# LED_drivers.net
KiCad netlist of a schematic drawn in Altium Designer
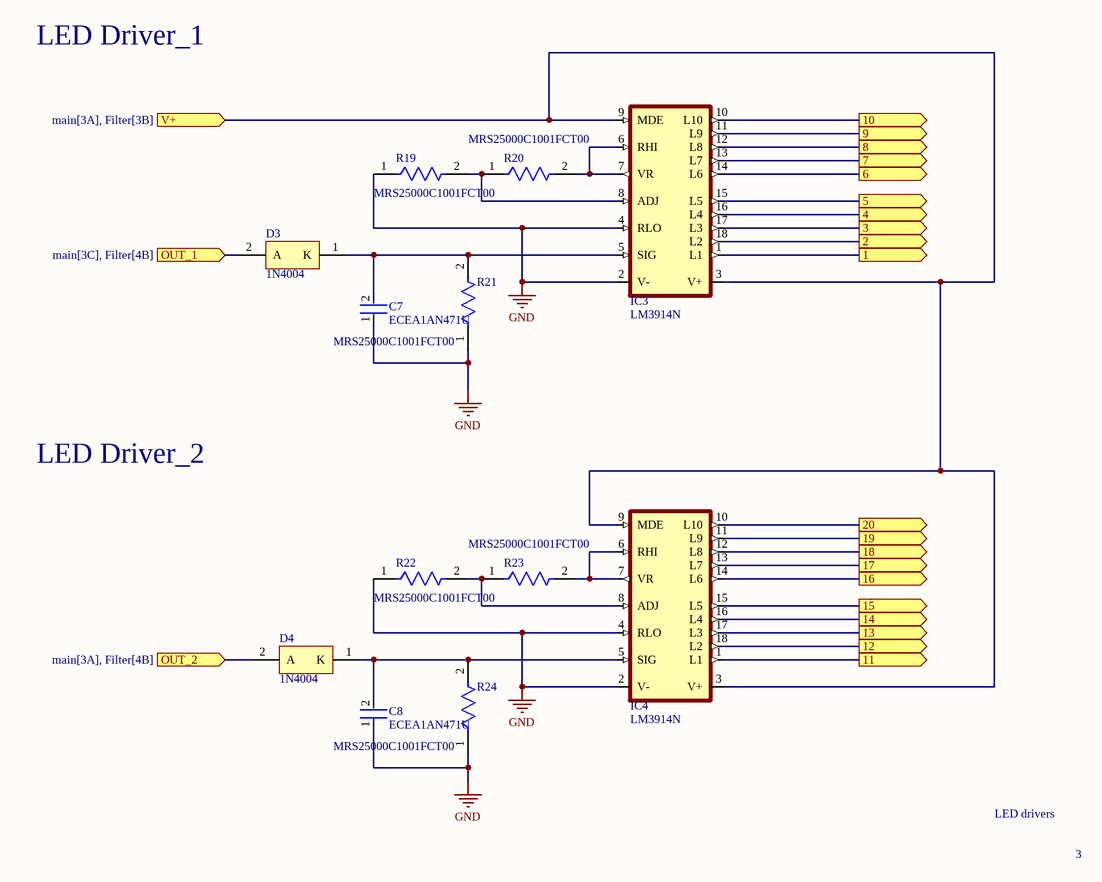
[diagram p0: LED drivers.SchDoc]

(export (version "E")
  (design (tool "Eeschema 10.0.6"))
  (components
    (comp (ref "C7")
      (value "ECEA1AN471U")
      (footprint "FP-RAD-TH-D_10_0_5-L_16_1-MFG")
      (description "Aluminum Electrolytic Capacitors (Radial Lead Type) 470uF ±20% 10V")
      (fields (field (name "TOLERANCE") "20%") (field (name "VOLTAGE") "10V"))
      (libsource (lib "Altium Content Vault") (part "02cd4be3c70576c341d710602a673aa"))
    )
    (comp (ref "C8")
      (value "ECEA1AN471U")
      (footprint "FP-RAD-TH-D_10_0_5-L_16_1-MFG")
      (description "Aluminum Electrolytic Capacitors (Radial Lead Type) 470uF ±20% 10V")
      (fields (field (name "TOLERANCE") "20%") (field (name "VOLTAGE") "10V"))
      (libsource (lib "Altium Content Vault") (part "02cd4be3c70576c341d710602a673aa"))
    )
    (comp (ref "D3")
      (value "1N4004")
      (footprint "ONSC-AXIAL_LEAD-2-59-10_P")
      (description "Standard Recovery Rectifier, 2-Pin Axial_Lead, Pb-Free, Bulk Bag")
      (fields (field (name "MANUFACTURER") "On Semiconductor"))
      (libsource (lib "Altium Content Vault") (part "ONSC-D-K1A2-2_A"))
    )
    (comp (ref "D4")
      (value "1N4004")
      (footprint "ONSC-AXIAL_LEAD-2-59-10_P")
      (description "Standard Recovery Rectifier, 2-Pin Axial_Lead, Pb-Free, Bulk Bag")
      (fields (field (name "MANUFACTURER") "On Semiconductor"))
      (libsource (lib "Altium Content Vault") (part "ONSC-D-K1A2-2_A"))
    )
    (comp (ref "IC3")
      (value "LM3914N")
      (footprint "DIL18")
      (description "LED Lighting Drivers")
      (fields (field (name "MF") "Texas Instruments"))
      (libsource (lib "LM3914N") (part "LM3914N"))
    )
    (comp (ref "IC4")
      (value "LM3914N")
      (footprint "DIL18")
      (description "LED Lighting Drivers")
      (fields (field (name "MF") "Texas Instruments"))
      (libsource (lib "LM3914N") (part "LM3914N"))
    )
    (comp (ref "R19")
      (value "MRS25000C1001FCT00")
      (footprint "FP-MRS25-MFG")
      (description "RES 1K OHM 0.6W 1% AXIAL")
      (fields (field (name "TOLERANCE") "1%"))
      (libsource (lib "Altium Content Vault") (part "1029c3af85768c4190bb7ad29bc67b5"))
    )
    (comp (ref "R20")
      (value "MRS25000C1001FCT00")
      (footprint "FP-MRS25-MFG")
      (description "RES 1K OHM 0.6W 1% AXIAL")
      (fields (field (name "TOLERANCE") "1%"))
      (libsource (lib "Altium Content Vault") (part "1029c3af85768c4190bb7ad29bc67b5"))
    )
    (comp (ref "R21")
      (value "MRS25000C1001FCT00")
      (footprint "FP-MRS25-MFG")
      (description "RES 1K OHM 0.6W 1% AXIAL")
      (fields (field (name "TOLERANCE") "1%"))
      (libsource (lib "Altium Content Vault") (part "1029c3af85768c4190bb7ad29bc67b5"))
    )
    (comp (ref "R22")
      (value "MRS25000C1001FCT00")
      (footprint "FP-MRS25-MFG")
      (description "RES 1K OHM 0.6W 1% AXIAL")
      (fields (field (name "TOLERANCE") "1%"))
      (libsource (lib "Altium Content Vault") (part "1029c3af85768c4190bb7ad29bc67b5"))
    )
    (comp (ref "R23")
      (value "MRS25000C1001FCT00")
      (footprint "FP-MRS25-MFG")
      (description "RES 1K OHM 0.6W 1% AXIAL")
      (fields (field (name "TOLERANCE") "1%"))
      (libsource (lib "Altium Content Vault") (part "1029c3af85768c4190bb7ad29bc67b5"))
    )
    (comp (ref "R24")
      (value "MRS25000C1001FCT00")
      (footprint "FP-MRS25-MFG")
      (description "RES 1K OHM 0.6W 1% AXIAL")
      (fields (field (name "TOLERANCE") "1%"))
      (libsource (lib "Altium Content Vault") (part "1029c3af85768c4190bb7ad29bc67b5"))
    )
  )
  (nets
    (net (code "1") (name "/1") (class "Default")
      (node (ref "IC3") (pin "1") (pinfunction "L1_1") (pintype "output"))
    )
    (net (code "2") (name "/2") (class "Default")
      (node (ref "IC3") (pin "18") (pinfunction "L2_18") (pintype "output"))
    )
    (net (code "3") (name "/3") (class "Default")
      (node (ref "IC3") (pin "17") (pinfunction "L3_17") (pintype "output"))
    )
    (net (code "4") (name "/4") (class "Default")
      (node (ref "IC3") (pin "16") (pinfunction "L4_16") (pintype "output"))
    )
    (net (code "5") (name "/5") (class "Default")
      (node (ref "IC3") (pin "15") (pinfunction "L5_15") (pintype "output"))
    )
    (net (code "6") (name "/6") (class "Default")
      (node (ref "IC3") (pin "14") (pinfunction "L6_14") (pintype "output"))
    )
    (net (code "7") (name "/7") (class "Default")
      (node (ref "IC3") (pin "13") (pinfunction "L7_13") (pintype "output"))
    )
    (net (code "8") (name "/8") (class "Default")
      (node (ref "IC3") (pin "12") (pinfunction "L8_12") (pintype "output"))
    )
    (net (code "9") (name "/9") (class "Default")
      (node (ref "IC3") (pin "11") (pinfunction "L9_11") (pintype "output"))
    )
    (net (code "10") (name "/10") (class "Default")
      (node (ref "IC3") (pin "10") (pinfunction "L10_10") (pintype "output"))
    )
    (net (code "11") (name "/11") (class "Default")
      (node (ref "IC4") (pin "1") (pinfunction "L1_1") (pintype "output"))
    )
    (net (code "12") (name "/12") (class "Default")
      (node (ref "IC4") (pin "18") (pinfunction "L2_18") (pintype "output"))
    )
    (net (code "13") (name "/13") (class "Default")
      (node (ref "IC4") (pin "17") (pinfunction "L3_17") (pintype "output"))
    )
    (net (code "14") (name "/14") (class "Default")
      (node (ref "IC4") (pin "16") (pinfunction "L4_16") (pintype "output"))
    )
    (net (code "15") (name "/15") (class "Default")
      (node (ref "IC4") (pin "15") (pinfunction "L5_15") (pintype "output"))
    )
    (net (code "16") (name "/16") (class "Default")
      (node (ref "IC4") (pin "14") (pinfunction "L6_14") (pintype "output"))
    )
    (net (code "17") (name "/17") (class "Default")
      (node (ref "IC4") (pin "13") (pinfunction "L7_13") (pintype "output"))
    )
    (net (code "18") (name "/18") (class "Default")
      (node (ref "IC4") (pin "12") (pinfunction "L8_12") (pintype "output"))
    )
    (net (code "19") (name "/19") (class "Default")
      (node (ref "IC4") (pin "11") (pinfunction "L9_11") (pintype "output"))
    )
    (net (code "20") (name "/20") (class "Default")
      (node (ref "IC4") (pin "10") (pinfunction "L10_10") (pintype "output"))
    )
    (net (code "21") (name "/OUT_1") (class "Default")
      (node (ref "D3") (pin "2") (pinfunction "A_2") (pintype "passive"))
    )
    (net (code "22") (name "/OUT_2") (class "Default")
      (node (ref "D4") (pin "2") (pinfunction "A_2") (pintype "passive"))
    )
    (net (code "23") (name "/V+") (class "Default")
      (node (ref "IC3") (pin "3") (pinfunction "V+_3") (pintype "power_in"))
      (node (ref "IC3") (pin "9") (pinfunction "MDE_9") (pintype "input"))
      (node (ref "IC4") (pin "3") (pinfunction "V+_3") (pintype "power_in"))
      (node (ref "IC4") (pin "9") (pinfunction "MDE_9") (pintype "input"))
    )
    (net (code "24") (name "GND") (class "Default")
      (node (ref "C7") (pin "1") (pinfunction "1_1") (pintype "passive"))
      (node (ref "C8") (pin "1") (pinfunction "1_1") (pintype "passive"))
      (node (ref "IC3") (pin "2") (pinfunction "V-_2") (pintype "power_in"))
      (node (ref "IC3") (pin "4") (pinfunction "RLO_4") (pintype "input"))
      (node (ref "IC4") (pin "2") (pinfunction "V-_2") (pintype "power_in"))
      (node (ref "IC4") (pin "4") (pinfunction "RLO_4") (pintype "input"))
      (node (ref "R19") (pin "1") (pinfunction "1_1") (pintype "passive"))
      (node (ref "R21") (pin "1") (pinfunction "1_1") (pintype "passive"))
      (node (ref "R22") (pin "1") (pinfunction "1_1") (pintype "passive"))
      (node (ref "R24") (pin "1") (pinfunction "1_1") (pintype "passive"))
    )
    (net (code "25") (name "Net-(D3-K)") (class "Default")
      (node (ref "C7") (pin "2") (pinfunction "2_2") (pintype "passive"))
      (node (ref "D3") (pin "1") (pinfunction "K_1") (pintype "passive"))
      (node (ref "IC3") (pin "5") (pinfunction "SIG_5") (pintype "input"))
      (node (ref "R21") (pin "2") (pinfunction "2_2") (pintype "passive"))
    )
    (net (code "26") (name "Net-(D4-K)") (class "Default")
      (node (ref "C8") (pin "2") (pinfunction "2_2") (pintype "passive"))
      (node (ref "D4") (pin "1") (pinfunction "K_1") (pintype "passive"))
      (node (ref "IC4") (pin "5") (pinfunction "SIG_5") (pintype "input"))
      (node (ref "R24") (pin "2") (pinfunction "2_2") (pintype "passive"))
    )
    (net (code "27") (name "Net-(IC3-ADJ)") (class "Default")
      (node (ref "IC3") (pin "8") (pinfunction "ADJ_8") (pintype "input"))
      (node (ref "R19") (pin "2") (pinfunction "2_2") (pintype "passive"))
      (node (ref "R20") (pin "1") (pinfunction "1_1") (pintype "passive"))
    )
    (net (code "28") (name "Net-(IC3-RHI)") (class "Default")
      (node (ref "IC3") (pin "6") (pinfunction "RHI_6") (pintype "input"))
      (node (ref "IC3") (pin "7") (pinfunction "VR_7") (pintype "output"))
      (node (ref "R20") (pin "2") (pinfunction "2_2") (pintype "passive"))
    )
    (net (code "29") (name "Net-(IC4-ADJ)") (class "Default")
      (node (ref "IC4") (pin "8") (pinfunction "ADJ_8") (pintype "input"))
      (node (ref "R22") (pin "2") (pinfunction "2_2") (pintype "passive"))
      (node (ref "R23") (pin "1") (pinfunction "1_1") (pintype "passive"))
    )
    (net (code "30") (name "Net-(IC4-RHI)") (class "Default")
      (node (ref "IC4") (pin "6") (pinfunction "RHI_6") (pintype "input"))
      (node (ref "IC4") (pin "7") (pinfunction "VR_7") (pintype "output"))
      (node (ref "R23") (pin "2") (pinfunction "2_2") (pintype "passive"))
    )
  )
)
